# EMF.net
KiCad netlist of a schematic drawn in EAGLE
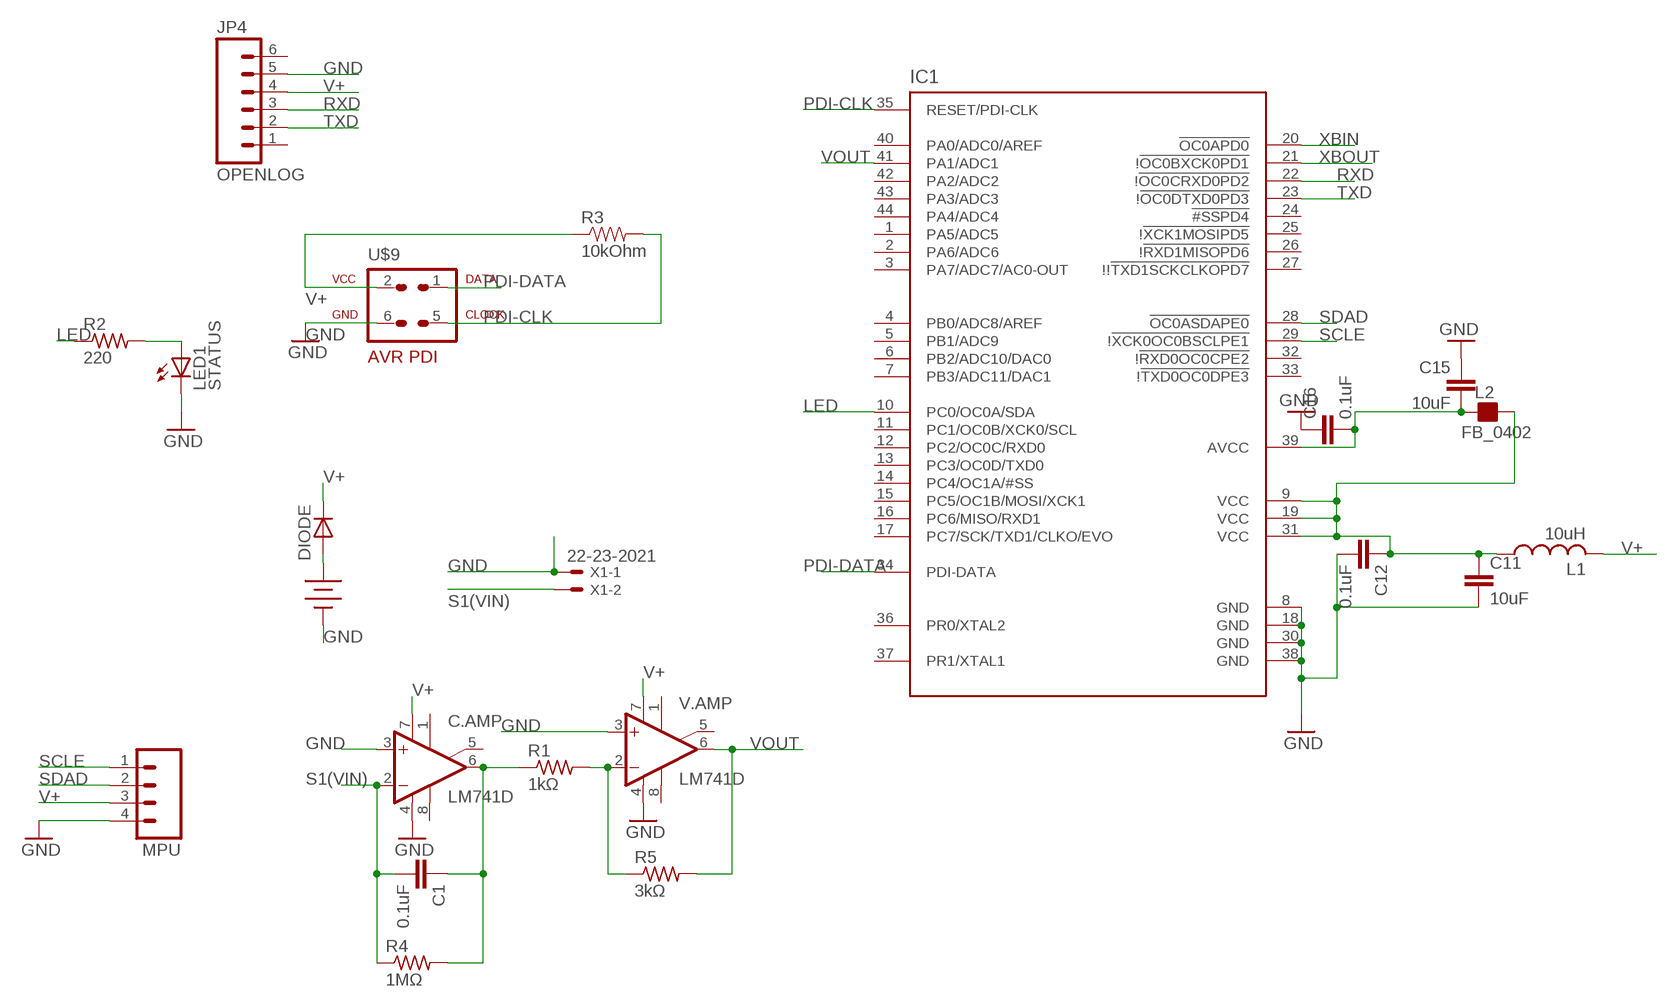
[diagram p0: schematic, sheet 1]

(export (version "E")
  (design (tool "Eeschema 10.0.6"))
  (components
    (comp (ref "C.AMP")
      (value "LM741D")
      (footprint "eagle-import:SO08")
      (libsource (lib "eagle-import") (part "741DLM"))
    )
    (comp (ref "C1")
      (value "0.1uF")
      (footprint "eagle-import:0805")
      (libsource (lib "eagle-import") (part "CAP0805"))
    )
    (comp (ref "C11")
      (value "10uF")
      (footprint "eagle-import:0805")
      (libsource (lib "eagle-import") (part "CAP0805"))
    )
    (comp (ref "C12")
      (value "0.1uF")
      (footprint "eagle-import:0805")
      (libsource (lib "eagle-import") (part "CAP0805"))
    )
    (comp (ref "C15")
      (value "10uF")
      (footprint "eagle-import:0805")
      (libsource (lib "eagle-import") (part "CAP0805"))
    )
    (comp (ref "C16")
      (value "0.1uF")
      (footprint "eagle-import:0805")
      (libsource (lib "eagle-import") (part "CAP0805"))
    )
    (comp (ref "DIODE")
      (value "LILYPAD-WEARABLES_LED1206")
      (footprint "eagle-import:LILYPAD-WEARABLES_LED-1206")
      (libsource (lib "eagle-import") (part "LILYPAD-WEARABLES_LED1206"))
    )
    (comp (ref "IC1")
      (value "AT-XMEGA-XXA4-AU")
      (footprint "eagle-import:QFP80P1200X1200X120-44N")
      (libsource (lib "eagle-import") (part "AT-XMEGA-XXA4-AU"))
    )
    (comp (ref "JP4")
      (value "OPENLOG")
      (footprint "eagle-import:MOLEX-1X6")
      (libsource (lib "eagle-import") (part "M06POLAR"))
    )
    (comp (ref "L1")
      (value "10uH")
      (footprint "eagle-import:L2012C")
      (libsource (lib "eagle-import") (part "L-USL2012C"))
    )
    (comp (ref "L2")
      (value "FB_0402")
      (footprint "eagle-import:L0402")
      (libsource (lib "eagle-import") (part "FB_0402"))
    )
    (comp (ref "LED1")
      (value "STATUS")
      (footprint "eagle-import:CHIP-LED0603")
      (libsource (lib "eagle-import") (part "LEDCHIP-LED0603"))
    )
    (comp (ref "MPU")
      (value "M04")
      (footprint "eagle-import:04P")
      (libsource (lib "eagle-import") (part "M04"))
    )
    (comp (ref "R1")
      (value "1kΩ")
      (footprint "eagle-import:M2012")
      (libsource (lib "eagle-import") (part "resistor_348_R-US_M2012"))
    )
    (comp (ref "R2")
      (value "220")
      (footprint "eagle-import:R0603")
      (libsource (lib "eagle-import") (part "R-US_R0603"))
    )
    (comp (ref "R3")
      (value "10kOhm")
      (footprint "eagle-import:0805")
      (libsource (lib "eagle-import") (part "RESISTOR0805-RES"))
    )
    (comp (ref "R4")
      (value "1MΩ")
      (footprint "eagle-import:M2012")
      (libsource (lib "eagle-import") (part "resistor_348_R-US_M2012"))
    )
    (comp (ref "R5")
      (value "3kΩ")
      (footprint "eagle-import:M2012")
      (libsource (lib "eagle-import") (part "resistor_348_R-US_M2012"))
    )
    (comp (ref "U$1")
      (value "SHC_123_BATTERY_HOLDERCR-123-A")
      (footprint "eagle-import:SHC_CR-123-A_HOLDER")
      (libsource (lib "eagle-import") (part "SHC_123_BATTERY_HOLDERCR-123-A"))
    )
    (comp (ref "U$9")
      (value "AVR-PDIVERT")
      (footprint "eagle-import:AVR-ISP-6")
      (libsource (lib "eagle-import") (part "AVR-PDIVERT"))
    )
    (comp (ref "V.AMP")
      (value "LM741D")
      (footprint "eagle-import:SO08")
      (fields (field (name "SPICEPREFIX") "X"))
      (libsource (lib "eagle-import") (part "741DLM"))
    )
    (comp (ref "X1")
      (value "22-23-2021")
      (footprint "eagle-import:22-23-2021")
      (fields (field (name "MF") "MOLEX"))
      (libsource (lib "eagle-import") (part "22-23-2021"))
    )
  )
  (nets
    (net (code "1") (name "/LED") (class "Default")
      (node (ref "IC1") (pin "10") (pinfunction "PC0/OC0A/SDA_10") (pintype "bidirectional"))
      (node (ref "R2") (pin "1") (pinfunction "1_1") (pintype "passive"))
    )
    (net (code "2") (name "/PDI-CLK") (class "Default")
      (node (ref "IC1") (pin "35") (pinfunction "RESET/PDI-CLK_35") (pintype "input"))
      (node (ref "R3") (pin "2") (pinfunction "2_2") (pintype "passive"))
      (node (ref "U$9") (pin "5") (pinfunction "5_5") (pintype "passive"))
    )
    (net (code "3") (name "/PDI-DATA") (class "Default")
      (node (ref "IC1") (pin "34") (pinfunction "PDI-DATA_34") (pintype "bidirectional"))
      (node (ref "U$9") (pin "1") (pinfunction "1_1") (pintype "passive"))
    )
    (net (code "4") (name "/RXD") (class "Default")
      (node (ref "IC1") (pin "22") (pinfunction "~OC0CRXD0PD2_22") (pintype "bidirectional"))
      (node (ref "JP4") (pin "3") (pinfunction "3_3") (pintype "passive"))
    )
    (net (code "5") (name "/S1(VIN)") (class "Default")
      (node (ref "C.AMP") (pin "2") (pinfunction "-IN_2") (pintype "input"))
      (node (ref "C1") (pin "2") (pinfunction "2_2") (pintype "passive"))
      (node (ref "R4") (pin "1") (pinfunction "1_1") (pintype "passive"))
      (node (ref "X1") (pin "2") (pinfunction "S_2") (pintype "passive"))
    )
    (net (code "6") (name "/SCLE") (class "Default")
      (node (ref "IC1") (pin "29") (pinfunction "~XCK0OC0BSCLPE1_29") (pintype "bidirectional"))
      (node (ref "MPU") (pin "1") (pinfunction "1_1") (pintype "passive"))
    )
    (net (code "7") (name "/SDAD") (class "Default")
      (node (ref "IC1") (pin "28") (pinfunction "~{OC0ASDAPE0}_28") (pintype "bidirectional"))
      (node (ref "MPU") (pin "2") (pinfunction "2_2") (pintype "passive"))
    )
    (net (code "8") (name "/TXD") (class "Default")
      (node (ref "IC1") (pin "23") (pinfunction "~OC0DTXD0PD3_23") (pintype "bidirectional"))
      (node (ref "JP4") (pin "2") (pinfunction "2_2") (pintype "passive"))
    )
    (net (code "9") (name "/V+") (class "Default")
      (node (ref "C.AMP") (pin "7") (pinfunction "V+_7") (pintype "power_in"))
      (node (ref "DIODE") (pin "C") (pinfunction "C_C") (pintype "passive"))
      (node (ref "JP4") (pin "4") (pinfunction "4_4") (pintype "passive"))
      (node (ref "L1") (pin "2") (pinfunction "2_2") (pintype "passive"))
      (node (ref "MPU") (pin "3") (pinfunction "3_3") (pintype "passive"))
      (node (ref "R3") (pin "1") (pinfunction "1_1") (pintype "passive"))
      (node (ref "U$9") (pin "2") (pinfunction "2_2") (pintype "passive"))
      (node (ref "V.AMP") (pin "7") (pinfunction "V+_7") (pintype "power_in"))
    )
    (net (code "10") (name "/VOUT") (class "Default")
      (node (ref "IC1") (pin "41") (pinfunction "PA1/ADC1_41") (pintype "bidirectional"))
      (node (ref "R5") (pin "2") (pinfunction "2_2") (pintype "passive"))
      (node (ref "V.AMP") (pin "6") (pinfunction "OUT_6") (pintype "output"))
    )
    (net (code "11") (name "/XBIN") (class "Default")
      (node (ref "IC1") (pin "20") (pinfunction "~{OC0APD0}_20") (pintype "bidirectional"))
    )
    (net (code "12") (name "/XBOUT") (class "Default")
      (node (ref "IC1") (pin "21") (pinfunction "~OC0BXCK0PD1_21") (pintype "bidirectional"))
    )
    (net (code "13") (name "GND") (class "Default")
      (node (ref "C.AMP") (pin "3") (pinfunction "+IN_3") (pintype "input"))
      (node (ref "C.AMP") (pin "4") (pinfunction "V-_4") (pintype "power_in"))
      (node (ref "C11") (pin "2") (pinfunction "2_2") (pintype "passive"))
      (node (ref "C12") (pin "2") (pinfunction "2_2") (pintype "passive"))
      (node (ref "C15") (pin "1") (pinfunction "1_1") (pintype "passive"))
      (node (ref "C16") (pin "1") (pinfunction "1_1") (pintype "passive"))
      (node (ref "IC1") (pin "18") (pinfunction "GND_18") (pintype "power_in"))
      (node (ref "IC1") (pin "30") (pinfunction "GND_30") (pintype "power_in"))
      (node (ref "IC1") (pin "38") (pinfunction "GND_38") (pintype "power_in"))
      (node (ref "IC1") (pin "8") (pinfunction "GND_8") (pintype "power_in"))
      (node (ref "JP4") (pin "5") (pinfunction "5_5") (pintype "passive"))
      (node (ref "LED1") (pin "C") (pinfunction "C_C") (pintype "passive"))
      (node (ref "MPU") (pin "4") (pinfunction "4_4") (pintype "passive"))
      (node (ref "U$1") (pin "-") (pinfunction "-_-") (pintype "bidirectional"))
      (node (ref "U$9") (pin "6") (pinfunction "6_6") (pintype "passive"))
      (node (ref "V.AMP") (pin "3") (pinfunction "+IN_3") (pintype "input"))
      (node (ref "V.AMP") (pin "4") (pinfunction "V-_4") (pintype "power_in"))
      (node (ref "X1") (pin "1") (pinfunction "S_1") (pintype "passive"))
    )
    (net (code "14") (name "Net-(C.AMP-OUT)") (class "Default")
      (node (ref "C.AMP") (pin "6") (pinfunction "OUT_6") (pintype "output"))
      (node (ref "C1") (pin "1") (pinfunction "1_1") (pintype "passive"))
      (node (ref "R1") (pin "1") (pinfunction "1_1") (pintype "passive"))
      (node (ref "R4") (pin "2") (pinfunction "2_2") (pintype "passive"))
    )
    (net (code "15") (name "Net-(C11-Pad1)") (class "Default")
      (node (ref "C11") (pin "1") (pinfunction "1_1") (pintype "passive"))
      (node (ref "C12") (pin "1") (pinfunction "1_1") (pintype "passive"))
      (node (ref "IC1") (pin "19") (pinfunction "VCC_19") (pintype "power_in"))
      (node (ref "IC1") (pin "31") (pinfunction "VCC_31") (pintype "power_in"))
      (node (ref "IC1") (pin "9") (pinfunction "VCC_9") (pintype "power_in"))
      (node (ref "L1") (pin "1") (pinfunction "1_1") (pintype "passive"))
      (node (ref "L2") (pin "2") (pinfunction "2_2") (pintype "passive"))
    )
    (net (code "16") (name "Net-(DIODE-PadA)") (class "Default")
      (node (ref "DIODE") (pin "A") (pinfunction "A_A") (pintype "passive"))
      (node (ref "U$1") (pin "+") (pinfunction "+_+") (pintype "bidirectional"))
    )
    (net (code "17") (name "Net-(IC1-AVCC)") (class "Default")
      (node (ref "C15") (pin "2") (pinfunction "2_2") (pintype "passive"))
      (node (ref "C16") (pin "2") (pinfunction "2_2") (pintype "passive"))
      (node (ref "IC1") (pin "39") (pinfunction "AVCC_39") (pintype "power_in"))
      (node (ref "L2") (pin "1") (pinfunction "1_1") (pintype "passive"))
    )
    (net (code "18") (name "Net-(LED1-PadA)") (class "Default")
      (node (ref "LED1") (pin "A") (pinfunction "A_A") (pintype "passive"))
      (node (ref "R2") (pin "2") (pinfunction "2_2") (pintype "passive"))
    )
    (net (code "19") (name "Net-(V.AMP--IN)") (class "Default")
      (node (ref "R1") (pin "2") (pinfunction "2_2") (pintype "passive"))
      (node (ref "R5") (pin "1") (pinfunction "1_1") (pintype "passive"))
      (node (ref "V.AMP") (pin "2") (pinfunction "-IN_2") (pintype "input"))
    )
    (net (code "20") (name "unconnected-(C.AMP-ON1-Pad1)") (class "Default")
      (node (ref "C.AMP") (pin "1") (pinfunction "ON1_1") (pintype "passive"))
    )
    (net (code "21") (name "unconnected-(C.AMP-ON2-Pad5)") (class "Default")
      (node (ref "C.AMP") (pin "5") (pinfunction "ON2_5") (pintype "passive"))
    )
    (net (code "22") (name "unconnected-(C.AMP-OPT-Pad8)") (class "Default")
      (node (ref "C.AMP") (pin "8") (pinfunction "OPT_8") (pintype "passive"))
    )
    (net (code "23") (name "unconnected-(IC1-PA0{slash}ADC0{slash}AREF-Pad40)") (class "Default")
      (node (ref "IC1") (pin "40") (pinfunction "PA0/ADC0/AREF_40") (pintype "bidirectional"))
    )
    (net (code "24") (name "unconnected-(IC1-PA2{slash}ADC2-Pad42)") (class "Default")
      (node (ref "IC1") (pin "42") (pinfunction "PA2/ADC2_42") (pintype "bidirectional"))
    )
    (net (code "25") (name "unconnected-(IC1-PA3{slash}ADC3-Pad43)") (class "Default")
      (node (ref "IC1") (pin "43") (pinfunction "PA3/ADC3_43") (pintype "bidirectional"))
    )
    (net (code "26") (name "unconnected-(IC1-PA4{slash}ADC4-Pad44)") (class "Default")
      (node (ref "IC1") (pin "44") (pinfunction "PA4/ADC4_44") (pintype "bidirectional"))
    )
    (net (code "27") (name "unconnected-(IC1-PA5{slash}ADC5-Pad1)") (class "Default")
      (node (ref "IC1") (pin "1") (pinfunction "PA5/ADC5_1") (pintype "bidirectional"))
    )
    (net (code "28") (name "unconnected-(IC1-PA6{slash}ADC6-Pad2)") (class "Default")
      (node (ref "IC1") (pin "2") (pinfunction "PA6/ADC6_2") (pintype "bidirectional"))
    )
    (net (code "29") (name "unconnected-(IC1-PA7{slash}ADC7{slash}AC0-OUT-Pad3)") (class "Default")
      (node (ref "IC1") (pin "3") (pinfunction "PA7/ADC7/AC0-OUT_3") (pintype "bidirectional"))
    )
    (net (code "30") (name "unconnected-(IC1-PB0{slash}ADC8{slash}AREF-Pad4)") (class "Default")
      (node (ref "IC1") (pin "4") (pinfunction "PB0/ADC8/AREF_4") (pintype "bidirectional"))
    )
    (net (code "31") (name "unconnected-(IC1-PB1{slash}ADC9-Pad5)") (class "Default")
      (node (ref "IC1") (pin "5") (pinfunction "PB1/ADC9_5") (pintype "bidirectional"))
    )
    (net (code "32") (name "unconnected-(IC1-PB2{slash}ADC10{slash}DAC0-Pad6)") (class "Default")
      (node (ref "IC1") (pin "6") (pinfunction "PB2/ADC10/DAC0_6") (pintype "bidirectional"))
    )
    (net (code "33") (name "unconnected-(IC1-PB3{slash}ADC11{slash}DAC1-Pad7)") (class "Default")
      (node (ref "IC1") (pin "7") (pinfunction "PB3/ADC11/DAC1_7") (pintype "bidirectional"))
    )
    (net (code "34") (name "unconnected-(IC1-PC1{slash}OC0B{slash}XCK0{slash}SCL-Pad11)") (class "Default")
      (node (ref "IC1") (pin "11") (pinfunction "PC1/OC0B/XCK0/SCL_11") (pintype "bidirectional"))
    )
    (net (code "35") (name "unconnected-(IC1-PC2{slash}OC0C{slash}RXD0-Pad12)") (class "Default")
      (node (ref "IC1") (pin "12") (pinfunction "PC2/OC0C/RXD0_12") (pintype "bidirectional"))
    )
    (net (code "36") (name "unconnected-(IC1-PC3{slash}OC0D{slash}TXD0-Pad13)") (class "Default")
      (node (ref "IC1") (pin "13") (pinfunction "PC3/OC0D/TXD0_13") (pintype "bidirectional"))
    )
    (net (code "37") (name "unconnected-(IC1-PC4{slash}OC1A{slash}#SS-Pad14)") (class "Default")
      (node (ref "IC1") (pin "14") (pinfunction "PC4/OC1A/#SS_14") (pintype "bidirectional"))
    )
    (net (code "38") (name "unconnected-(IC1-PC5{slash}OC1B{slash}MOSI{slash}XCK1-Pad15)") (class "Default")
      (node (ref "IC1") (pin "15") (pinfunction "PC5/OC1B/MOSI/XCK1_15") (pintype "bidirectional"))
    )
    (net (code "39") (name "unconnected-(IC1-PC6{slash}MISO{slash}RXD1-Pad16)") (class "Default")
      (node (ref "IC1") (pin "16") (pinfunction "PC6/MISO/RXD1_16") (pintype "bidirectional"))
    )
    (net (code "40") (name "unconnected-(IC1-PC7{slash}SCK{slash}TXD1{slash}CLKO{slash}EVO-Pad17)") (class "Default")
      (node (ref "IC1") (pin "17") (pinfunction "PC7/SCK/TXD1/CLKO/EVO_17") (pintype "bidirectional"))
    )
    (net (code "41") (name "unconnected-(IC1-PR0{slash}XTAL2-Pad36)") (class "Default")
      (node (ref "IC1") (pin "36") (pinfunction "PR0/XTAL2_36") (pintype "bidirectional"))
    )
    (net (code "42") (name "unconnected-(IC1-PR1{slash}XTAL1-Pad37)") (class "Default")
      (node (ref "IC1") (pin "37") (pinfunction "PR1/XTAL1_37") (pintype "bidirectional"))
    )
    (net (code "43") (name "unconnected-(IC1-~RXD0OC0CPE2-Pad32)") (class "Default")
      (node (ref "IC1") (pin "32") (pinfunction "~RXD0OC0CPE2_32") (pintype "bidirectional"))
    )
    (net (code "44") (name "unconnected-(IC1-~RXD1MISOPD6-Pad26)") (class "Default")
      (node (ref "IC1") (pin "26") (pinfunction "~RXD1MISOPD6_26") (pintype "bidirectional"))
    )
    (net (code "45") (name "unconnected-(IC1-~TXD0OC0DPE3-Pad33)") (class "Default")
      (node (ref "IC1") (pin "33") (pinfunction "~TXD0OC0DPE3_33") (pintype "bidirectional"))
    )
    (net (code "46") (name "unconnected-(IC1-~XCK1MOSIPD5-Pad25)") (class "Default")
      (node (ref "IC1") (pin "25") (pinfunction "~XCK1MOSIPD5_25") (pintype "bidirectional"))
    )
    (net (code "47") (name "unconnected-(IC1-~{#SSPD4}-Pad24)") (class "Default")
      (node (ref "IC1") (pin "24") (pinfunction "~{#SSPD4}_24") (pintype "bidirectional"))
    )
    (net (code "48") (name "unconnected-(IC1-~~{TXD1SCKCLKOPD7}-Pad27)") (class "Default")
      (node (ref "IC1") (pin "27") (pinfunction "~~{TXD1SCKCLKOPD7}_27") (pintype "bidirectional"))
    )
    (net (code "49") (name "unconnected-(JP4-Pad1)") (class "Default")
      (node (ref "JP4") (pin "1") (pinfunction "1_1") (pintype "passive"))
    )
    (net (code "50") (name "unconnected-(JP4-Pad6)") (class "Default")
      (node (ref "JP4") (pin "6") (pinfunction "6_6") (pintype "passive"))
    )
    (net (code "51") (name "unconnected-(V.AMP-ON1-Pad1)") (class "Default")
      (node (ref "V.AMP") (pin "1") (pinfunction "ON1_1") (pintype "passive"))
    )
    (net (code "52") (name "unconnected-(V.AMP-ON2-Pad5)") (class "Default")
      (node (ref "V.AMP") (pin "5") (pinfunction "ON2_5") (pintype "passive"))
    )
    (net (code "53") (name "unconnected-(V.AMP-OPT-Pad8)") (class "Default")
      (node (ref "V.AMP") (pin "8") (pinfunction "OPT_8") (pintype "passive"))
    )
  )
)
